# LV_BUCK.net
KiCad netlist of a schematic drawn in Altium Designer
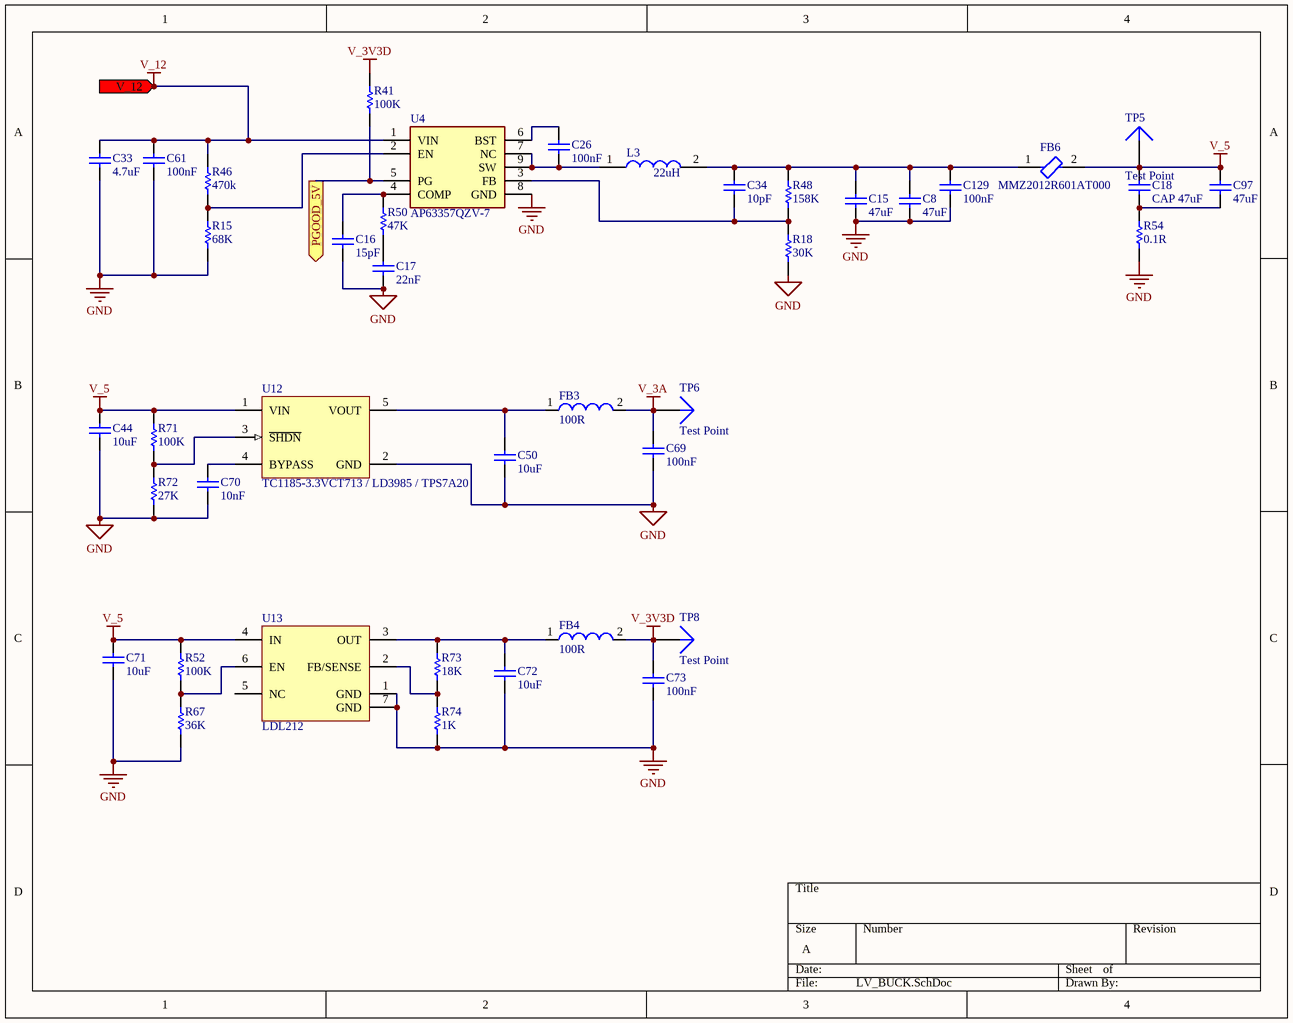
[diagram p0: LV_BUCK.SchDoc]

(export (version "E")
  (design (tool "Eeschema 10.0.6"))
  (components
    (comp (ref "C8")
      (value "47uF")
      (footprint "CAPC1206(3216)190_N")
      (description "X5R 47uF ±20% 10V 1206 Multilayer Ceramic Capacitors MLCC - SMD/SMT ROHS")
      (fields (field (name "TOLERANCE") "Â±10%") (field (name "MANUFACTURER") "Kyocera AVX"))
      (libsource (lib "DCDC") (part "CAP"))
    )
    (comp (ref "C15")
      (value "47uF")
      (footprint "CAPC1206(3216)190_N")
      (description "X5R 47uF ±20% 10V 1206 Multilayer Ceramic Capacitors MLCC - SMD/SMT ROHS")
      (fields (field (name "TOLERANCE") "Â±10%") (field (name "MANUFACTURER") "Kyocera AVX"))
      (libsource (lib "DCDC") (part "CAP"))
    )
    (comp (ref "C16")
      (value "15pF")
      (footprint "CAPC1005X56X25NL10T15")
      (description "C0G ±5% 15pF 50V 0402 Multilayer Ceramic Capacitors MLCC - SMD/SMT ROHS")
      (fields
        (field (name "MANUFACTURER") "AVX Interconnect / Elco")
        (field (name "PART NUMBER") "04025A150FAT2A")
      )
      (libsource (lib "Altium Content Vault") (part "CAP"))
    )
    (comp (ref "C17")
      (value "22nF")
      (footprint "CAPC1005X56X25NL10T15")
      (description "X7R ±10% 50V 22nF 0402 Multilayer Ceramic Capacitors MLCC - SMD/SMT ROHS")
      (fields
        (field (name "MANUFACTURER") "AVX Interconnect / Elco")
        (field (name "PART NUMBER") "04023C103JAT2A")
      )
      (libsource (lib "Altium Content Vault") (part "CAP"))
    )
    (comp (ref "C18")
      (value "CAP 47uF")
      (footprint "CAPC1210(3225)280_M")
      (description "CAP 47uF 6.3V ±20% 1210 (3225 Metric) Thickness 2.8mm SMD")
      (fields (field (name "TOLERANCE") "Â±20%"))
      (libsource (lib "Altium Content Vault") (part "CAP"))
    )
    (comp (ref "C26")
      (value "100nF")
      (footprint "CAPC1005X56X25NL10T15")
      (description "X7R 100nF ±10% 16V 0402 Multilayer Ceramic Capacitors MLCC - SMD/SMT ROHS")
      (fields
        (field (name "MANUFACTURER") "AVX Interconnect / Elco")
        (field (name "PART NUMBER") "0402YC104KAT2A")
      )
      (libsource (lib "Altium Content Vault") (part "CAP"))
    )
    (comp (ref "C33")
      (value "4.7uF")
      (footprint "CAPC3216X180X50NL20T25")
      (description "X7R ±10% 50V 4.7uF 1206 Multilayer Ceramic Capacitors MLCC - SMD/SMT ROHS")
      (fields (field (name "TOLERANCE") "10%") (field (name "MANUFACTURER") "AVX"))
      (libsource (lib "Altium Content Vault") (part "CAP-NP-2"))
    )
    (comp (ref "C34")
      (value "10pF")
      (footprint "CAPC1005X56X25NL10T15")
      (description "C0G ±5% 10pF 50V 0402 Multilayer Ceramic Capacitors MLCC - SMD/SMT ROHS")
      (fields
        (field (name "PART NUMBER") "04025A100DAT2A")
        (field (name "MANUFACTURER") "AVX Interconnect / Elco")
      )
      (libsource (lib "Altium Content Vault") (part "CAP"))
    )
    (comp (ref "C44")
      (value "10uF")
      (footprint "CAPC2013X140X45NL15T25")
      (description "X5R 25V ±10% 10uF 0805 Multilayer Ceramic Capacitors MLCC - SMD/SMT ROHS")
      (fields (field (name "PART NUMBER") "GRM21BR71A106KE51L") (field (name "MANUFACTURER") "Murata"))
      (libsource (lib "Altium Content Vault") (part "CAP"))
    )
    (comp (ref "C50")
      (value "10uF")
      (footprint "CAPC2013X140X45NL15T25")
      (description "X5R 25V ±10% 10uF 0805 Multilayer Ceramic Capacitors MLCC - SMD/SMT ROHS")
      (fields (field (name "PART NUMBER") "GRM21BR71A106KE51L") (field (name "MANUFACTURER") "Murata"))
      (libsource (lib "Altium Content Vault") (part "CAP"))
    )
    (comp (ref "C61")
      (value "100nF")
      (footprint "CAPC1608X90X35NL10T15")
      (description "X7R 100nF ±10% 50V 0603 Multilayer Ceramic Capacitors MLCC - SMD/SMT ROHS")
      (fields (field (name "PART NUMBER") "GCM188R72A104KA64D") (field (name "MANUFACTURER") "Murata"))
      (libsource (lib "DCDC") (part "CAP"))
    )
    (comp (ref "C69")
      (value "100nF")
      (footprint "CAPC1608X90X35NL10T15")
      (description "X7R 100nF ±10% 50V 0603 Multilayer Ceramic Capacitors MLCC - SMD/SMT ROHS")
      (fields (field (name "PART NUMBER") "GCM188R72A104KA64D") (field (name "MANUFACTURER") "Murata"))
      (libsource (lib "DCDC") (part "CAP"))
    )
    (comp (ref "C70")
      (value "10nF")
      (footprint "CAPC1608X90X35NL10T15")
      (description "X7R ±10% 50V 10nF 0603 Multilayer Ceramic Capacitors MLCC - SMD/SMT ROHS")
      (fields (field (name "PART NUMBER") "GRM188R71H472KA01D") (field (name "MANUFACTURER") "Murata"))
      (libsource (lib "DCDC") (part "CMP-2006-02924-1"))
    )
    (comp (ref "C71")
      (value "10uF")
      (footprint "CAPC2013X140X45NL15T25")
      (description "X5R 25V ±10% 10uF 0805 Multilayer Ceramic Capacitors MLCC - SMD/SMT ROHS")
      (fields (field (name "PART NUMBER") "GRM21BR71A106KE51L") (field (name "MANUFACTURER") "Murata"))
      (libsource (lib "Altium Content Vault") (part "CAP"))
    )
    (comp (ref "C72")
      (value "10uF")
      (footprint "CAPC2013X140X45NL15T25")
      (description "X5R 25V ±10% 10uF 0805 Multilayer Ceramic Capacitors MLCC - SMD/SMT ROHS")
      (fields (field (name "PART NUMBER") "GRM21BR71A106KE51L") (field (name "MANUFACTURER") "Murata"))
      (libsource (lib "Altium Content Vault") (part "CAP"))
    )
    (comp (ref "C73")
      (value "100nF")
      (footprint "CAPC1608X90X35NL10T15")
      (description "X7R 100nF ±10% 50V 0603 Multilayer Ceramic Capacitors MLCC - SMD/SMT ROHS")
      (fields (field (name "PART NUMBER") "GCM188R72A104KA64D") (field (name "MANUFACTURER") "Murata"))
      (libsource (lib "DCDC") (part "CAP"))
    )
    (comp (ref "C97")
      (value "47uF")
      (footprint "CAPC1206(3216)190_N")
      (description "X5R 47uF ±20% 10V 1206 Multilayer Ceramic Capacitors MLCC - SMD/SMT ROHS")
      (fields (field (name "TOLERANCE") "Â±10%") (field (name "MANUFACTURER") "Kyocera AVX"))
      (libsource (lib "DCDC") (part "CAP"))
    )
    (comp (ref "C129")
      (value "100nF")
      (footprint "CAPC1005X56X25NL10T15")
      (description "X7R 100nF ±10% 16V 0402 Multilayer Ceramic Capacitors MLCC - SMD/SMT ROHS")
      (fields
        (field (name "MANUFACTURER") "AVX Interconnect / Elco")
        (field (name "PART NUMBER") "04026D104KAT2A")
      )
      (libsource (lib "DCDC") (part "CAP"))
    )
    (comp (ref "FB3")
      (value "100R")
      (footprint "SMD-0603")
      (description "SMD EMI Suppression Ferrite Bead WE-CBF, Z = 1500 Ohm")
      (libsource (lib "Altium Content Vault") (part "PAS-IND-INDUCTOR-2"))
    )
    (comp (ref "FB4")
      (value "100R")
      (footprint "SMD-0603")
      (description "SMD EMI Suppression Ferrite Bead WE-CBF, Z = 1500 Ohm")
      (libsource (lib "Altium Content Vault") (part "PAS-IND-INDUCTOR-2"))
    )
    (comp (ref "FB6")
      (value "MMZ2012R601AT000")
      (footprint "FP-MMZ2012-IPC_A")
      (description "Signal Line Ferrite Bead 600Ω @ 100Mhz 500mA DCR 200mΩ SMD 0805")
      (fields (field (name "TOLERANCE") "25%"))
      (libsource (lib "Altium Content Vault") (part "5f30dd21d616792df468990f7003faa"))
    )
    (comp (ref "L3")
      (value "22uH")
      (footprint "SamacSys:INDPM8680X400N")
      (description "Inductor 22uH")
      (fields
        (field (name "MANUFACTURER_PART_NUMBER") "MPX1D0840L220")
        (field (name "MOUSER PART NUMBER") "80-MPX1D0840L220")
      )
      (libsource (lib "*") (part "MPX1D0840L470"))
    )
    (comp (ref "R15")
      (value "68K")
      (footprint "RESC1005X40X25NL05T05")
      (description "1/16W ±1% ±100ppm/℃ 68kΩ 0402 Chip Resistor - Surface Mount ROHS")
      (fields (field (name "PART NUMBER") "ERJ-2RKF4993X") (field (name "MANUFACTURER") "Panasonic"))
      (libsource (lib "Altium Content Vault") (part "RES"))
    )
    (comp (ref "R18")
      (value "30K")
      (footprint "RESC1005X40X25NL05T05")
      (description "Res Thick Film 0402 30K Ohm 1% 0.063W(1/16W) ±100ppm/C Molded SMD Automotive Paper T/R")
      (fields (field (name "PART NUMBER") "CRCW040230K0FKED") (field (name "MANUFACTURER") "Vishay Dale"))
      (libsource (lib "Altium Content Vault") (part "RES"))
    )
    (comp (ref "R41")
      (value "100K")
      (footprint "RESC1005X40X25NL05T10")
      (description "1/16W ±1% ±100ppm/℃ 100kΩ 0402 Chip Resistor - Surface Mount ROHS")
      (fields (field (name "PART NUMBER") "RC0402FR-07100KL") (field (name "MANUFACTURER") "Yageo / Phycomp"))
      (libsource (lib "Altium Content Vault") (part "RES"))
    )
    (comp (ref "R46")
      (value "470k")
      (footprint "RESC1005X40X25NL05T05")
      (description "±1% 1/16W 470kΩ ±100ppm/℃ 0402 Chip Resistor - Surface Mount ROHS")
      (fields (field (name "PART NUMBER") "ERJ-2RKF4993X") (field (name "MANUFACTURER") "Panasonic"))
      (libsource (lib "Altium Content Vault") (part "RES"))
    )
    (comp (ref "R48")
      (value "158K")
      (footprint "RESC1005X40X25NL05T05")
      (description "RES SMD 158K OHM 1% 1/16W 0402")
      (fields (field (name "MANUFACTURER") "Vishay Dale") (field (name "PART NUMBER") "CRCW0402158KFKTD"))
      (libsource (lib "Altium Content Vault") (part "RES"))
    )
    (comp (ref "R50")
      (value "47K")
      (footprint "RESC1005X40X25NL05T05")
      (description "1/16W ±1% ±100ppm/℃ 47kΩ 0402 Chip Resistor - Surface Mount ROHS")
      (fields (field (name "PART NUMBER") "CRCW040242K2FKED") (field (name "MANUFACTURER") "Vishay Dale"))
      (libsource (lib "Altium Content Vault") (part "RES"))
    )
    (comp (ref "R52")
      (value "100K")
      (footprint "RESC1608X55X25NL10T15")
      (description "±1% 100kΩ ±100ppm/℃ 0.1W 0603 Chip Resistor - Surface Mount ROHS")
      (fields (field (name "MANUFACTURER") "Yageo") (field (name "TOLERANCE") "1%"))
      (libsource (lib "DCDC") (part "CMP-2100-03662-1"))
    )
    (comp (ref "R54")
      (value "0.1R")
      (footprint "RESC1608X55X25ML10T15")
      (description "Chip Resistor, 0 Ohm, +/- 5%, 0.1 W, -55 to 155 degC, 0603 (1608 Metric), RoHS, Tape and Reel")
      (fields (field (name "TOLERANCE") "5%") (field (name "MANUFACTURER") "Yageo"))
      (libsource (lib "Altium Content Vault") (part "RES-2"))
    )
    (comp (ref "R67")
      (value "36K")
      (footprint "RESC1608X55X25NL10T15")
      (description "36kΩ ±1% ±100ppm/℃ 0.1W 0603 Chip Resistor - Surface Mount ROHS")
      (fields (field (name "MANUFACTURER") "Yageo") (field (name "TOLERANCE") "1%"))
      (libsource (lib "DCDC") (part "CMP-2100-03662-1"))
    )
    (comp (ref "R71")
      (value "100K")
      (footprint "RESC1608X55X25NL10T15")
      (description "±1% 100kΩ ±100ppm/℃ 0.1W 0603 Chip Resistor - Surface Mount ROHS")
      (fields (field (name "MANUFACTURER") "Yageo") (field (name "TOLERANCE") "1%"))
      (libsource (lib "DCDC") (part "CMP-2100-03662-1"))
    )
    (comp (ref "R72")
      (value "27K")
      (footprint "RESC1608X55X25NL10T15")
      (description "±1% ±100ppm/℃ 0.1W 27kΩ 0603 Chip Resistor - Surface Mount ROHS")
      (fields (field (name "MANUFACTURER") "Yageo") (field (name "TOLERANCE") "1%"))
      (libsource (lib "DCDC") (part "CMP-2100-03662-1"))
    )
    (comp (ref "R73")
      (value "18K")
      (footprint "RESC1608X55X30NL20T20")
      (description "18kΩ ±1% ±100ppm/℃ 0.1W 0603 Chip Resistor - Surface Mount ROHS")
      (fields (field (name "MANUFACTURER") "Panasonic") (field (name "PART NUMBER") "ERA3AEB183V"))
      (libsource (lib "Altium Content Vault") (part "RES"))
    )
    (comp (ref "R74")
      (value "1K")
      (footprint "RESC1608X55X30NL15T15")
      (description "±1% ±100ppm/℃ 1kΩ 0.1W 0603 Chip Resistor - Surface Mount ROHS")
      (fields (field (name "PART NUMBER") "ERJ-3EKF1001V") (field (name "MANUFACTURER") "Panasonic"))
      (libsource (lib "Altium Content Vault") (part "RES"))
    )
    (comp (ref "TP5")
      (value "Test Point")
      (footprint "TP1.5mm")
      (description "Round Test Point")
      (fields (field (name "PUBLISHER") "Altium Limited"))
      (libsource (lib "DCDC") (part "Test_Point 1.5mm round"))
    )
    (comp (ref "TP6")
      (value "Test Point")
      (footprint "TP1.5mm")
      (description "Round Test Point")
      (fields (field (name "PUBLISHER") "Altium Limited"))
      (libsource (lib "DCDC") (part "Test_Point 1.5mm round"))
    )
    (comp (ref "TP8")
      (value "Test Point")
      (footprint "TP1.5mm")
      (description "Round Test Point")
      (fields (field (name "PUBLISHER") "Altium Limited"))
      (libsource (lib "DCDC") (part "Test_Point 1.5mm round"))
    )
    (comp (ref "U4")
      (value "AP63357QZV-7")
      (footprint "SamacSys:AP63357QZV7")
      (description "Integrated Circuit")
      (fields (field (name "MOUSER PART NUMBER") "621-AP63357QZV-7"))
      (libsource (lib "*") (part "AP63357QZV-7"))
    )
    (comp (ref "U12")
      (value "TC1185-3.3VCT713 / LD3985 / TPS7A20")
      (footprint "SOT23-5")
      (libsource (lib "PBL - Integrated Circuits") (part "PM-LINEREG-TC1014-IL5"))
    )
    (comp (ref "U13") (value "LDL212") (footprint "LDL212PUR") (libsource (lib "LDL212") (part "LDL212")))
  )
  (nets
    (net (code "1") (name "/PGOOD_5V") (class "Default")
      (node (ref "R41") (pin "1") (pinfunction "1_1") (pintype "passive"))
      (node (ref "U4") (pin "5") (pinfunction "PG_5") (pintype "passive"))
    )
    (net (code "2") (name "GND") (class "Default")
      (node (ref "C129") (pin "1") (pinfunction "1_1") (pintype "passive"))
      (node (ref "C15") (pin "1") (pinfunction "1_1") (pintype "passive"))
      (node (ref "C16") (pin "1") (pinfunction "1_1") (pintype "passive"))
      (node (ref "C17") (pin "1") (pinfunction "1_1") (pintype "passive"))
      (node (ref "C33") (pin "1") (pinfunction "1_1") (pintype "passive"))
      (node (ref "C44") (pin "1") (pinfunction "1_1") (pintype "passive"))
      (node (ref "C50") (pin "1") (pinfunction "1_1") (pintype "passive"))
      (node (ref "C61") (pin "1") (pinfunction "1_1") (pintype "passive"))
      (node (ref "C69") (pin "1") (pinfunction "1_1") (pintype "passive"))
      (node (ref "C70") (pin "1") (pinfunction "1_1") (pintype "passive"))
      (node (ref "C71") (pin "1") (pinfunction "1_1") (pintype "passive"))
      (node (ref "C72") (pin "1") (pinfunction "1_1") (pintype "passive"))
      (node (ref "C73") (pin "1") (pinfunction "1_1") (pintype "passive"))
      (node (ref "C8") (pin "1") (pinfunction "1_1") (pintype "passive"))
      (node (ref "R15") (pin "1") (pinfunction "1_1") (pintype "passive"))
      (node (ref "R18") (pin "1") (pinfunction "1_1") (pintype "passive"))
      (node (ref "R54") (pin "1") (pinfunction "1_1") (pintype "passive"))
      (node (ref "R67") (pin "1") (pinfunction "1_1") (pintype "passive"))
      (node (ref "R72") (pin "1") (pinfunction "1_1") (pintype "passive"))
      (node (ref "R74") (pin "1") (pinfunction "1_1") (pintype "passive"))
      (node (ref "U12") (pin "2") (pinfunction "GND_2") (pintype "power_in"))
      (node (ref "U13") (pin "1") (pinfunction "GND_1") (pintype "passive"))
      (node (ref "U13") (pin "7") (pinfunction "GND_7") (pintype "passive"))
      (node (ref "U4") (pin "8") (pinfunction "GND_8") (pintype "passive"))
    )
    (net (code "3") (name "Net-(C17-Pad2)") (class "Default")
      (node (ref "C17") (pin "2") (pinfunction "2_2") (pintype "passive"))
      (node (ref "R50") (pin "1") (pinfunction "1_1") (pintype "passive"))
    )
    (net (code "4") (name "Net-(C18-Pad1)") (class "Default")
      (node (ref "C18") (pin "1") (pinfunction "1_1") (pintype "passive"))
      (node (ref "C97") (pin "1") (pinfunction "1_1") (pintype "passive"))
      (node (ref "R54") (pin "2") (pinfunction "2_2") (pintype "passive"))
    )
    (net (code "5") (name "Net-(C129-Pad2)") (class "Default")
      (node (ref "C129") (pin "2") (pinfunction "2_2") (pintype "passive"))
      (node (ref "C15") (pin "2") (pinfunction "2_2") (pintype "passive"))
      (node (ref "C34") (pin "2") (pinfunction "2_2") (pintype "passive"))
      (node (ref "C8") (pin "2") (pinfunction "2_2") (pintype "passive"))
      (node (ref "FB6") (pin "1") (pinfunction "1_1") (pintype "passive"))
      (node (ref "L3") (pin "2") (pinfunction "2_2") (pintype "passive"))
      (node (ref "R48") (pin "2") (pinfunction "2_2") (pintype "passive"))
    )
    (net (code "6") (name "Net-(U4-BST)") (class "Default")
      (node (ref "C26") (pin "2") (pinfunction "2_2") (pintype "passive"))
      (node (ref "U4") (pin "6") (pinfunction "BST_6") (pintype "passive"))
    )
    (net (code "7") (name "Net-(U4-COMP)") (class "Default")
      (node (ref "C16") (pin "2") (pinfunction "2_2") (pintype "passive"))
      (node (ref "R50") (pin "2") (pinfunction "2_2") (pintype "passive"))
      (node (ref "U4") (pin "4") (pinfunction "COMP_4") (pintype "passive"))
    )
    (net (code "8") (name "Net-(U4-EN)") (class "Default")
      (node (ref "R15") (pin "2") (pinfunction "2_2") (pintype "passive"))
      (node (ref "R46") (pin "1") (pinfunction "1_1") (pintype "passive"))
      (node (ref "U4") (pin "2") (pinfunction "EN_2") (pintype "passive"))
    )
    (net (code "9") (name "Net-(U4-FB)") (class "Default")
      (node (ref "C34") (pin "1") (pinfunction "1_1") (pintype "passive"))
      (node (ref "R18") (pin "2") (pinfunction "2_2") (pintype "passive"))
      (node (ref "R48") (pin "1") (pinfunction "1_1") (pintype "passive"))
      (node (ref "U4") (pin "3") (pinfunction "FB_3") (pintype "passive"))
    )
    (net (code "10") (name "Net-(U4-NC)") (class "Default")
      (node (ref "C26") (pin "1") (pinfunction "1_1") (pintype "passive"))
      (node (ref "L3") (pin "1") (pinfunction "1_1") (pintype "passive"))
      (node (ref "U4") (pin "7") (pinfunction "NC_7") (pintype "passive"))
      (node (ref "U4") (pin "9") (pinfunction "SW_9") (pintype "passive"))
    )
    (net (code "11") (name "Net-(U12-BYPASS)") (class "Default")
      (node (ref "C70") (pin "2") (pinfunction "2_2") (pintype "passive"))
      (node (ref "U12") (pin "4") (pinfunction "BYPASS_4") (pintype "passive"))
    )
    (net (code "12") (name "Net-(U12-VOUT)") (class "Default")
      (node (ref "C50") (pin "2") (pinfunction "2_2") (pintype "passive"))
      (node (ref "FB3") (pin "1") (pinfunction "1_1") (pintype "passive"))
      (node (ref "U12") (pin "5") (pinfunction "VOUT_5") (pintype "power_in"))
    )
    (net (code "13") (name "Net-(U12-~{SHDN})") (class "Default")
      (node (ref "R71") (pin "1") (pinfunction "1_1") (pintype "passive"))
      (node (ref "R72") (pin "2") (pinfunction "2_2") (pintype "passive"))
      (node (ref "U12") (pin "3") (pinfunction "~{SHDN}_3") (pintype "input"))
    )
    (net (code "14") (name "Net-(U13-EN)") (class "Default")
      (node (ref "R52") (pin "1") (pinfunction "1_1") (pintype "passive"))
      (node (ref "R67") (pin "2") (pinfunction "2_2") (pintype "passive"))
      (node (ref "U13") (pin "6") (pinfunction "EN_6") (pintype "passive"))
    )
    (net (code "15") (name "Net-(U13-FB{slash}SENSE)") (class "Default")
      (node (ref "R73") (pin "1") (pinfunction "1_1") (pintype "passive"))
      (node (ref "R74") (pin "2") (pinfunction "2_2") (pintype "passive"))
      (node (ref "U13") (pin "2") (pinfunction "FB/SENSE_2") (pintype "passive"))
    )
    (net (code "16") (name "Net-(U13-OUT)") (class "Default")
      (node (ref "C72") (pin "2") (pinfunction "2_2") (pintype "passive"))
      (node (ref "FB4") (pin "1") (pinfunction "1_1") (pintype "passive"))
      (node (ref "R73") (pin "2") (pinfunction "2_2") (pintype "passive"))
      (node (ref "U13") (pin "3") (pinfunction "OUT_3") (pintype "passive"))
    )
    (net (code "17") (name "V_3A") (class "Default")
      (node (ref "C69") (pin "2") (pinfunction "2_2") (pintype "passive"))
      (node (ref "FB3") (pin "2") (pinfunction "2_2") (pintype "passive"))
      (node (ref "TP6") (pin "1") (pinfunction "1_1") (pintype "passive"))
    )
    (net (code "18") (name "V_3V3D") (class "Default")
      (node (ref "C73") (pin "2") (pinfunction "2_2") (pintype "passive"))
      (node (ref "FB4") (pin "2") (pinfunction "2_2") (pintype "passive"))
      (node (ref "R41") (pin "2") (pinfunction "2_2") (pintype "passive"))
      (node (ref "TP8") (pin "1") (pinfunction "1_1") (pintype "passive"))
    )
    (net (code "19") (name "V_5") (class "Default")
      (node (ref "C18") (pin "2") (pinfunction "2_2") (pintype "passive"))
      (node (ref "C44") (pin "2") (pinfunction "2_2") (pintype "passive"))
      (node (ref "C71") (pin "2") (pinfunction "2_2") (pintype "passive"))
      (node (ref "C97") (pin "2") (pinfunction "2_2") (pintype "passive"))
      (node (ref "FB6") (pin "2") (pinfunction "2_2") (pintype "passive"))
      (node (ref "R52") (pin "2") (pinfunction "2_2") (pintype "passive"))
      (node (ref "R71") (pin "2") (pinfunction "2_2") (pintype "passive"))
      (node (ref "TP5") (pin "1") (pinfunction "1_1") (pintype "passive"))
      (node (ref "U12") (pin "1") (pinfunction "VIN_1") (pintype "power_in"))
      (node (ref "U13") (pin "4") (pinfunction "IN_4") (pintype "passive"))
    )
    (net (code "20") (name "V_12") (class "Default")
      (node (ref "C33") (pin "2") (pinfunction "2_2") (pintype "passive"))
      (node (ref "C61") (pin "2") (pinfunction "2_2") (pintype "passive"))
      (node (ref "R46") (pin "2") (pinfunction "2_2") (pintype "passive"))
      (node (ref "U4") (pin "1") (pinfunction "VIN_1") (pintype "passive"))
    )
    (net (code "21") (name "unconnected-(U13-NC-Pad5)") (class "Default")
      (node (ref "U13") (pin "5") (pinfunction "NC_5") (pintype "passive"))
    )
  )
)
